# nand3.net
KiCad netlist of a schematic drawn in EAGLE
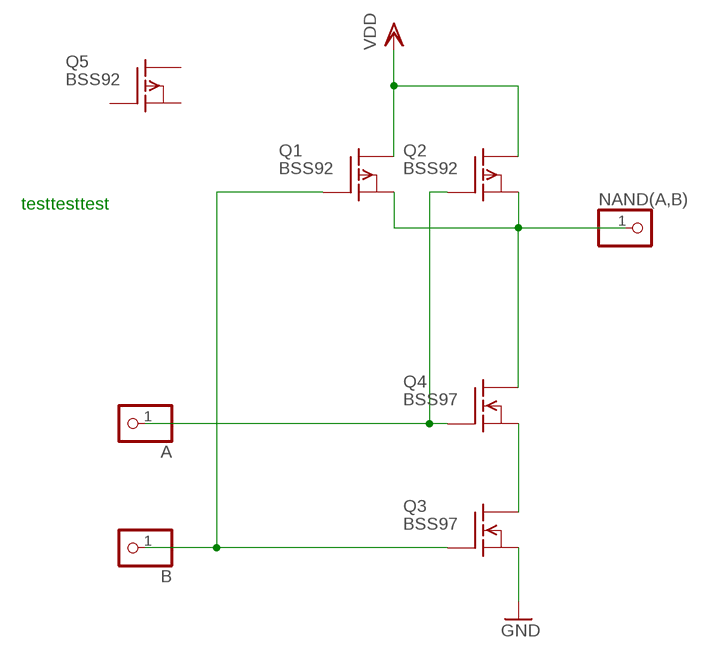
[diagram p0: schematic, sheet 1]

(export (version "E")
  (design (tool "Eeschema 10.0.6"))
  (components
    (comp (ref "A")
      (value "PINHD-1X1")
      (footprint "eagle-import:1X01")
      (libsource (lib "eagle-import") (part "PINHD-1X1"))
    )
    (comp (ref "B")
      (value "PINHD-1X1")
      (footprint "eagle-import:1X01")
      (libsource (lib "eagle-import") (part "PINHD-1X1"))
    )
    (comp (ref "NAND(A,B)")
      (value "PINHD-1X1")
      (footprint "eagle-import:1X01")
      (libsource (lib "eagle-import") (part "PINHD-1X1"))
    )
    (comp (ref "Q1")
      (value "BSS92")
      (footprint "eagle-import:TO92")
      (libsource (lib "eagle-import") (part "BSS92"))
    )
    (comp (ref "Q2")
      (value "BSS92")
      (footprint "eagle-import:TO92")
      (libsource (lib "eagle-import") (part "BSS92"))
    )
    (comp (ref "Q3")
      (value "BSS97")
      (footprint "eagle-import:TO202")
      (libsource (lib "eagle-import") (part "BSS97"))
    )
    (comp (ref "Q4")
      (value "BSS97")
      (footprint "eagle-import:TO202")
      (libsource (lib "eagle-import") (part "BSS97"))
    )
    (comp (ref "Q5")
      (value "BSS92")
      (footprint "eagle-import:TO92")
      (libsource (lib "eagle-import") (part "BSS92"))
    )
  )
  (nets
    (net (code "1") (name "GND") (class "Default")
      (node (ref "Q3") (pin "1") (pinfunction "S_1") (pintype "passive"))
    )
    (net (code "2") (name "Net-(Q1-G)") (class "Default")
      (node (ref "B") (pin "1") (pinfunction "1_1") (pintype "passive"))
      (node (ref "Q1") (pin "1") (pinfunction "G_1") (pintype "passive"))
      (node (ref "Q3") (pin "3") (pinfunction "G_3") (pintype "passive"))
    )
    (net (code "3") (name "Net-(Q1-S)") (class "Default")
      (node (ref "NAND(A,B)") (pin "1") (pinfunction "1_1") (pintype "passive"))
      (node (ref "Q1") (pin "3") (pinfunction "S_3") (pintype "passive"))
      (node (ref "Q2") (pin "3") (pinfunction "S_3") (pintype "passive"))
      (node (ref "Q4") (pin "2") (pinfunction "D_2") (pintype "passive"))
    )
    (net (code "4") (name "Net-(Q2-G)") (class "Default")
      (node (ref "A") (pin "1") (pinfunction "1_1") (pintype "passive"))
      (node (ref "Q2") (pin "1") (pinfunction "G_1") (pintype "passive"))
      (node (ref "Q4") (pin "3") (pinfunction "G_3") (pintype "passive"))
    )
    (net (code "5") (name "Net-(Q3-D)") (class "Default")
      (node (ref "Q3") (pin "2") (pinfunction "D_2") (pintype "passive"))
      (node (ref "Q4") (pin "1") (pinfunction "S_1") (pintype "passive"))
    )
    (net (code "6") (name "VDD") (class "Default")
      (node (ref "Q1") (pin "2") (pinfunction "D_2") (pintype "passive"))
      (node (ref "Q2") (pin "2") (pinfunction "D_2") (pintype "passive"))
    )
    (net (code "7") (name "unconnected-(Q5-D-Pad2)") (class "Default")
      (node (ref "Q5") (pin "2") (pinfunction "D_2") (pintype "passive"))
    )
    (net (code "8") (name "unconnected-(Q5-G-Pad1)") (class "Default")
      (node (ref "Q5") (pin "1") (pinfunction "G_1") (pintype "passive"))
    )
    (net (code "9") (name "unconnected-(Q5-S-Pad3)") (class "Default")
      (node (ref "Q5") (pin "3") (pinfunction "S_3") (pintype "passive"))
    )
  )
)
